# Wifi.net
KiCad netlist of a schematic drawn in Altium Designer
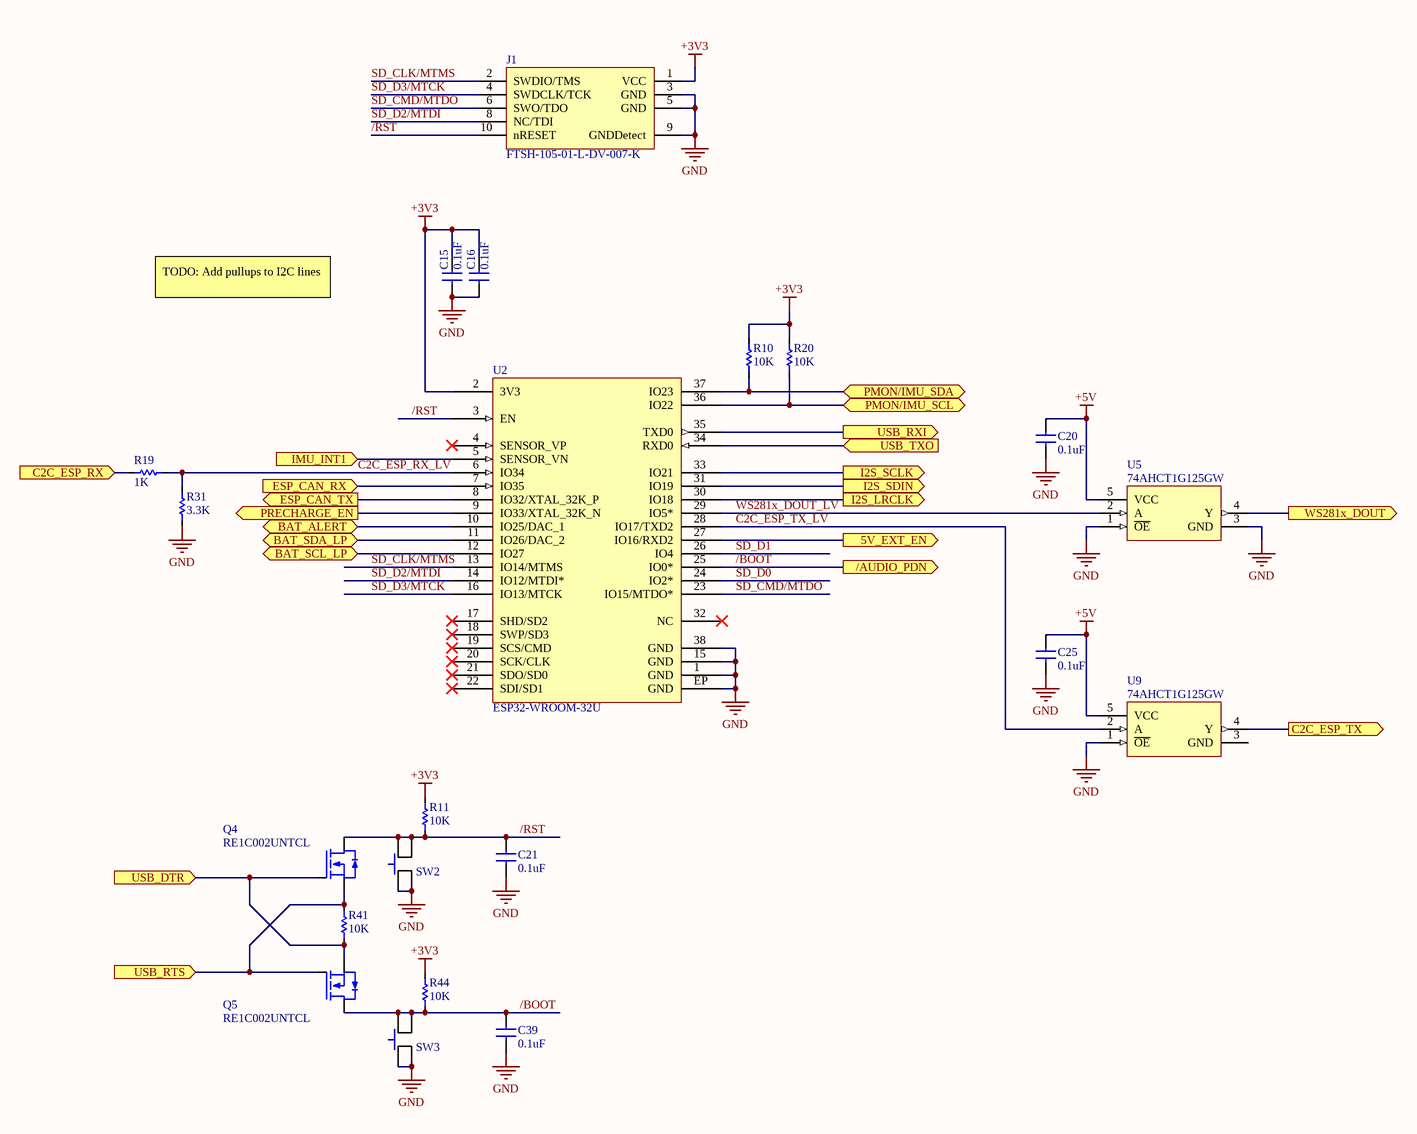
[diagram p0: Wifi.SchDoc]

(export (version "E")
  (design (tool "Eeschema 10.0.6"))
  (components
    (comp (ref "C15")
      (value "0.1uF")
      (footprint "0402_CAPACITOR")
      (description "CAP CERM 0.1uF 10% 16V 0402")
      (fields (field (name "VOLTAGE") "16V") (field (name "Comment") "CAP 0.1uF 16V X7R"))
      (libsource (lib "capacitor") (part "C_0402_0.1uF_16V_10%"))
    )
    (comp (ref "C16")
      (value "0.1uF")
      (footprint "0402_CAPACITOR")
      (description "CAP CERM 0.1uF 10% 16V 0402")
      (fields (field (name "VOLTAGE") "16V") (field (name "Comment") "CAP 0.1uF 16V X7R"))
      (libsource (lib "capacitor") (part "C_0402_0.1uF_16V_10%"))
    )
    (comp (ref "C20")
      (value "0.1uF")
      (footprint "0402_CAPACITOR")
      (description "CAP CERM 0.1uF 10% 16V 0402")
      (fields (field (name "VOLTAGE") "16V") (field (name "Comment") "CAP 0.1uF 16V X7R"))
      (libsource (lib "capacitor") (part "C_0402_0.1uF_16V_10%"))
    )
    (comp (ref "C21")
      (value "0.1uF")
      (footprint "0402_CAPACITOR")
      (description "CAP CERM 0.1uF 10% 16V 0402")
      (fields (field (name "VOLTAGE") "16V") (field (name "Comment") "CAP 0.1uF 16V X7R"))
      (libsource (lib "capacitor") (part "C_0402_0.1uF_16V_10%"))
    )
    (comp (ref "C25")
      (value "0.1uF")
      (footprint "0402_CAPACITOR")
      (description "CAP CERM 0.1uF 10% 16V 0402")
      (fields (field (name "VOLTAGE") "16V") (field (name "Comment") "CAP 0.1uF 16V X7R"))
      (libsource (lib "capacitor") (part "C_0402_0.1uF_16V_10%"))
    )
    (comp (ref "C39")
      (value "0.1uF")
      (footprint "0402_CAPACITOR")
      (description "CAP CERM 0.1uF 10% 16V 0402")
      (fields (field (name "VOLTAGE") "16V") (field (name "Comment") "CAP 0.1uF 16V X7R"))
      (libsource (lib "capacitor") (part "C_0402_0.1uF_16V_10%"))
    )
    (comp (ref "J1")
      (value "FTSH-105-01-L-DV-007-K")
      (footprint "J_Cortex_JTAG_SMD")
      (description "CORTEX JTAG DEBUG CONNECTOR")
      (fields (field (name "MANUFACTURER") "Samtec Inc"))
      (libsource (lib "connector") (part "J_Cortex_JTAG_SMD"))
    )
    (comp (ref "Q4")
      (value "RE1C002UNTCL")
      (footprint "EMT3F")
      (description "N-Channel 20V 200mA (Ta) 150mW (Ta) Surface Mount EMT3F (SOT-416FL)")
      (fields (field (name "MANUFACTURER") "Rohm"))
      (libsource (lib "transistor") (part "Q_RE1C002UNTCL"))
    )
    (comp (ref "Q5")
      (value "RE1C002UNTCL")
      (footprint "EMT3F")
      (description "N-Channel 20V 200mA (Ta) 150mW (Ta) Surface Mount EMT3F (SOT-416FL)")
      (fields (field (name "MANUFACTURER") "Rohm"))
      (libsource (lib "transistor") (part "Q_RE1C002UNTCL"))
    )
    (comp (ref "R10")
      (value "10K")
      (footprint "0402_Resistor")
      (description "Generic 0402 Resistor (10.2R to 10M)")
      (fields (field (name "TOLERANCE") "±1%") (field (name "MANUFACTURER") "Yageo"))
      (libsource (lib "resistor") (part "R_0402_generic_1%"))
    )
    (comp (ref "R11")
      (value "10K")
      (footprint "0402_Resistor")
      (description "Generic 0402 Resistor (10.2R to 10M)")
      (fields (field (name "TOLERANCE") "±1%") (field (name "MANUFACTURER") "Yageo"))
      (libsource (lib "resistor") (part "R_0402_generic_1%"))
    )
    (comp (ref "R19")
      (value "1K")
      (footprint "0402_Resistor")
      (description "Generic 0402 Resistor (10.2R to 10M)")
      (fields (field (name "TOLERANCE") "±1%") (field (name "MANUFACTURER") "Yageo"))
      (libsource (lib "resistor") (part "R_0402_generic_1%"))
    )
    (comp (ref "R20")
      (value "10K")
      (footprint "0402_Resistor")
      (description "Generic 0402 Resistor (10.2R to 10M)")
      (fields (field (name "TOLERANCE") "±1%") (field (name "MANUFACTURER") "Yageo"))
      (libsource (lib "resistor") (part "R_0402_generic_1%"))
    )
    (comp (ref "R31")
      (value "3.3K")
      (footprint "0402_Resistor")
      (description "Generic 0402 Resistor (10.2R to 10M)")
      (fields (field (name "TOLERANCE") "±1%") (field (name "MANUFACTURER") "Yageo"))
      (libsource (lib "resistor") (part "R_0402_generic_1%"))
    )
    (comp (ref "R41")
      (value "10K")
      (footprint "0402_Resistor")
      (description "Generic 0402 Resistor (10.2R to 10M)")
      (fields (field (name "TOLERANCE") "±1%") (field (name "MANUFACTURER") "Yageo"))
      (libsource (lib "resistor") (part "R_0402_generic_1%"))
    )
    (comp (ref "R44")
      (value "10K")
      (footprint "0402_Resistor")
      (description "Generic 0402 Resistor (10.2R to 10M)")
      (fields (field (name "TOLERANCE") "±1%") (field (name "MANUFACTURER") "Yageo"))
      (libsource (lib "resistor") (part "R_0402_generic_1%"))
    )
    (comp (ref "SW2")
      (value "KSEM31J_LFS")
      (footprint "SW_6x6mm_SMD")
      (description "Tactile Switch SPST-NO Top Actuated Surface Mount")
      (libsource (lib "misc") (part "SW_KSEM31J_LFS"))
    )
    (comp (ref "SW3")
      (value "KSEM31J_LFS")
      (footprint "SW_6x6mm_SMD")
      (description "Tactile Switch SPST-NO Top Actuated Surface Mount")
      (libsource (lib "misc") (part "SW_KSEM31J_LFS"))
    )
    (comp (ref "U2")
      (value "ESP32-WROOM-32U")
      (footprint "U_ESP32-WROOM-32U")
      (libsource (lib "ic") (part "U_ESP32-WROOM-32U"))
    )
    (comp (ref "U5")
      (value "74AHCT1G125GW")
      (footprint "SC70-5")
      (description "Buffer, Non-Inverting 1 Element 1 Bit per Element 3-State Output 5-TSSOP")
      (fields (field (name "MANUFACTURER") "NXP Semiconductors"))
      (libsource (lib "ic") (part "U_74AHCT1G125GW"))
    )
    (comp (ref "U9")
      (value "74AHCT1G125GW")
      (footprint "SC70-5")
      (description "Buffer, Non-Inverting 1 Element 1 Bit per Element 3-State Output 5-TSSOP")
      (fields (field (name "MANUFACTURER") "NXP Semiconductors"))
      (libsource (lib "ic") (part "U_74AHCT1G125GW"))
    )
  )
  (nets
    (net (code "1") (name "+3V3") (class "Default")
      (node (ref "C15") (pin "1") (pinfunction "1_1") (pintype "passive"))
      (node (ref "C16") (pin "1") (pinfunction "1_1") (pintype "passive"))
      (node (ref "J1") (pin "1") (pinfunction "VCC_1") (pintype "passive"))
      (node (ref "R10") (pin "1") (pinfunction "1_1") (pintype "passive"))
      (node (ref "R11") (pin "1") (pinfunction "1_1") (pintype "passive"))
      (node (ref "R20") (pin "1") (pinfunction "1_1") (pintype "passive"))
      (node (ref "R44") (pin "1") (pinfunction "1_1") (pintype "passive"))
      (node (ref "U2") (pin "2") (pinfunction "3V3_2") (pintype "power_in"))
    )
    (net (code "2") (name "+5V") (class "Default")
      (node (ref "C20") (pin "2") (pinfunction "2_2") (pintype "passive"))
      (node (ref "C25") (pin "2") (pinfunction "2_2") (pintype "passive"))
      (node (ref "U5") (pin "5") (pinfunction "VCC_5") (pintype "power_in"))
      (node (ref "U9") (pin "5") (pinfunction "VCC_5") (pintype "power_in"))
    )
    (net (code "3") (name "/5V_EXT_EN") (class "Default")
      (node (ref "U2") (pin "27") (pinfunction "IO16/RXD2_27") (pintype "passive"))
    )
    (net (code "4") (name "/BAT_ALERT") (class "Default")
      (node (ref "U2") (pin "10") (pinfunction "IO25/DAC_1_10") (pintype "passive"))
    )
    (net (code "5") (name "/BAT_SCL_LP") (class "Default")
      (node (ref "U2") (pin "12") (pinfunction "IO27_12") (pintype "passive"))
    )
    (net (code "6") (name "/BAT_SDA_LP") (class "Default")
      (node (ref "U2") (pin "11") (pinfunction "IO26/DAC_2_11") (pintype "passive"))
    )
    (net (code "7") (name "/C2C_ESP_RX") (class "Default")
      (node (ref "R19") (pin "1") (pinfunction "1_1") (pintype "passive"))
    )
    (net (code "8") (name "/C2C_ESP_RX_LV") (class "Default")
      (node (ref "R19") (pin "2") (pinfunction "2_2") (pintype "passive"))
      (node (ref "R31") (pin "2") (pinfunction "2_2") (pintype "passive"))
      (node (ref "U2") (pin "6") (pinfunction "IO34_6") (pintype "input"))
    )
    (net (code "9") (name "/C2C_ESP_TX") (class "Default")
      (node (ref "U9") (pin "4") (pinfunction "Y_4") (pintype "output"))
    )
    (net (code "10") (name "/C2C_ESP_TX_LV") (class "Default")
      (node (ref "U2") (pin "28") (pinfunction "IO17/TXD2_28") (pintype "passive"))
      (node (ref "U9") (pin "2") (pinfunction "A_2") (pintype "input"))
    )
    (net (code "11") (name "/ESP_CAN_RX") (class "Default")
      (node (ref "U2") (pin "7") (pinfunction "IO35_7") (pintype "input"))
    )
    (net (code "12") (name "/ESP_CAN_TX") (class "Default")
      (node (ref "U2") (pin "8") (pinfunction "IO32/XTAL_32K_P_8") (pintype "passive"))
    )
    (net (code "13") (name "/I2S_LRCLK") (class "Default")
      (node (ref "U2") (pin "30") (pinfunction "IO18_30") (pintype "passive"))
    )
    (net (code "14") (name "/I2S_SCLK") (class "Default")
      (node (ref "U2") (pin "33") (pinfunction "IO21_33") (pintype "passive"))
    )
    (net (code "15") (name "/I2S_SDIN") (class "Default")
      (node (ref "U2") (pin "31") (pinfunction "IO19_31") (pintype "passive"))
    )
    (net (code "16") (name "/IMU_INT1") (class "Default")
      (node (ref "U2") (pin "5") (pinfunction "SENSOR_VN_5") (pintype "input"))
    )
    (net (code "17") (name "/PMON{slash}IMU_SCL") (class "Default")
      (node (ref "R20") (pin "2") (pinfunction "2_2") (pintype "passive"))
      (node (ref "U2") (pin "36") (pinfunction "IO22_36") (pintype "passive"))
    )
    (net (code "18") (name "/PMON{slash}IMU_SDA") (class "Default")
      (node (ref "R10") (pin "2") (pinfunction "2_2") (pintype "passive"))
      (node (ref "U2") (pin "37") (pinfunction "IO23_37") (pintype "passive"))
    )
    (net (code "19") (name "/PRECHARGE_EN") (class "Default")
      (node (ref "U2") (pin "9") (pinfunction "IO33/XTAL_32K_N_9") (pintype "passive"))
    )
    (net (code "20") (name "/SD_CLK{slash}MTMS") (class "Default")
      (node (ref "J1") (pin "2") (pinfunction "SWDIO/TMS_2") (pintype "passive"))
      (node (ref "U2") (pin "13") (pinfunction "IO14/MTMS_13") (pintype "passive"))
    )
    (net (code "21") (name "/SD_CMD{slash}MTDO") (class "Default")
      (node (ref "J1") (pin "6") (pinfunction "SWO/TDO_6") (pintype "passive"))
      (node (ref "U2") (pin "23") (pinfunction "IO15/MTDO*_23") (pintype "passive"))
    )
    (net (code "22") (name "/SD_D0") (class "Default")
      (node (ref "U2") (pin "24") (pinfunction "IO2*_24") (pintype "passive"))
    )
    (net (code "23") (name "/SD_D1") (class "Default")
      (node (ref "U2") (pin "26") (pinfunction "IO4_26") (pintype "passive"))
    )
    (net (code "24") (name "/SD_D2{slash}MTDI") (class "Default")
      (node (ref "J1") (pin "8") (pinfunction "NC/TDI_8") (pintype "passive"))
      (node (ref "U2") (pin "14") (pinfunction "IO12/MTDI*_14") (pintype "passive"))
    )
    (net (code "25") (name "/SD_D3{slash}MTCK") (class "Default")
      (node (ref "J1") (pin "4") (pinfunction "SWDCLK/TCK_4") (pintype "passive"))
      (node (ref "U2") (pin "16") (pinfunction "IO13/MTCK_16") (pintype "passive"))
    )
    (net (code "26") (name "/USB_DTR") (class "Default")
      (node (ref "Q4") (pin "1") (pinfunction "GATE_1") (pintype "passive"))
      (node (ref "Q5") (pin "2") (pinfunction "SOURCE_2") (pintype "passive"))
      (node (ref "R41") (pin "2") (pinfunction "2_2") (pintype "passive"))
    )
    (net (code "27") (name "/USB_RTS") (class "Default")
      (node (ref "Q4") (pin "2") (pinfunction "SOURCE_2") (pintype "passive"))
      (node (ref "Q5") (pin "1") (pinfunction "GATE_1") (pintype "passive"))
      (node (ref "R41") (pin "1") (pinfunction "1_1") (pintype "passive"))
    )
    (net (code "28") (name "/USB_RXI") (class "Default")
      (node (ref "U2") (pin "35") (pinfunction "TXD0_35") (pintype "output"))
    )
    (net (code "29") (name "/USB_TXO") (class "Default")
      (node (ref "U2") (pin "34") (pinfunction "RXD0_34") (pintype "input"))
    )
    (net (code "30") (name "/WS281x_DOUT") (class "Default")
      (node (ref "U5") (pin "4") (pinfunction "Y_4") (pintype "output"))
    )
    (net (code "31") (name "/WS281x_DOUT_LV") (class "Default")
      (node (ref "U2") (pin "29") (pinfunction "IO5*_29") (pintype "passive"))
      (node (ref "U5") (pin "2") (pinfunction "A_2") (pintype "input"))
    )
    (net (code "32") (name "/{slash}BOOT") (class "Default")
      (node (ref "C39") (pin "2") (pinfunction "2_2") (pintype "passive"))
      (node (ref "Q5") (pin "3") (pinfunction "DRAIN_3") (pintype "passive"))
      (node (ref "R44") (pin "2") (pinfunction "2_2") (pintype "passive"))
      (node (ref "SW3") (pin "2") (pinfunction "2_2") (pintype "passive"))
      (node (ref "SW3") (pin "3") (pinfunction "3_3") (pintype "passive"))
      (node (ref "U2") (pin "25") (pinfunction "IO0*_25") (pintype "passive"))
    )
    (net (code "33") (name "/{slash}RST") (class "Default")
      (node (ref "C21") (pin "2") (pinfunction "2_2") (pintype "passive"))
      (node (ref "J1") (pin "10") (pinfunction "nRESET_10") (pintype "passive"))
      (node (ref "Q4") (pin "3") (pinfunction "DRAIN_3") (pintype "passive"))
      (node (ref "R11") (pin "2") (pinfunction "2_2") (pintype "passive"))
      (node (ref "SW2") (pin "2") (pinfunction "2_2") (pintype "passive"))
      (node (ref "SW2") (pin "3") (pinfunction "3_3") (pintype "passive"))
      (node (ref "U2") (pin "3") (pinfunction "EN_3") (pintype "input"))
    )
    (net (code "34") (name "GND") (class "Default")
      (node (ref "C15") (pin "2") (pinfunction "2_2") (pintype "passive"))
      (node (ref "C16") (pin "2") (pinfunction "2_2") (pintype "passive"))
      (node (ref "C20") (pin "1") (pinfunction "1_1") (pintype "passive"))
      (node (ref "C21") (pin "1") (pinfunction "1_1") (pintype "passive"))
      (node (ref "C25") (pin "1") (pinfunction "1_1") (pintype "passive"))
      (node (ref "C39") (pin "1") (pinfunction "1_1") (pintype "passive"))
      (node (ref "J1") (pin "3") (pinfunction "GND_3") (pintype "passive"))
      (node (ref "J1") (pin "5") (pinfunction "GND_5") (pintype "passive"))
      (node (ref "J1") (pin "9") (pinfunction "GNDDetect_9") (pintype "passive"))
      (node (ref "R31") (pin "1") (pinfunction "1_1") (pintype "passive"))
      (node (ref "SW2") (pin "1") (pinfunction "1_1") (pintype "passive"))
      (node (ref "SW2") (pin "4") (pinfunction "4_4") (pintype "passive"))
      (node (ref "SW3") (pin "1") (pinfunction "1_1") (pintype "passive"))
      (node (ref "SW3") (pin "4") (pinfunction "4_4") (pintype "passive"))
      (node (ref "U2") (pin "1") (pinfunction "GND_1") (pintype "power_in"))
      (node (ref "U2") (pin "15") (pinfunction "GND_15") (pintype "power_in"))
      (node (ref "U2") (pin "38") (pinfunction "GND_38") (pintype "power_in"))
      (node (ref "U2") (pin "EP") (pinfunction "GND_EP") (pintype "power_in"))
      (node (ref "U5") (pin "1") (pinfunction "~{OE}_1") (pintype "input"))
      (node (ref "U5") (pin "3") (pinfunction "GND_3") (pintype "power_in"))
      (node (ref "U9") (pin "1") (pinfunction "~{OE}_1") (pintype "input"))
    )
    (net (code "35") (name "unconnected-(U2-NC-Pad32)") (class "Default")
      (node (ref "U2") (pin "32") (pinfunction "NC_32") (pintype "tri_state+no_connect"))
    )
    (net (code "36") (name "unconnected-(U2-SCK{slash}CLK-Pad20)") (class "Default")
      (node (ref "U2") (pin "20") (pinfunction "SCK/CLK_20") (pintype "passive+no_connect"))
    )
    (net (code "37") (name "unconnected-(U2-SCS{slash}CMD-Pad19)") (class "Default")
      (node (ref "U2") (pin "19") (pinfunction "SCS/CMD_19") (pintype "passive+no_connect"))
    )
    (net (code "38") (name "unconnected-(U2-SDI{slash}SD1-Pad22)") (class "Default")
      (node (ref "U2") (pin "22") (pinfunction "SDI/SD1_22") (pintype "passive+no_connect"))
    )
    (net (code "39") (name "unconnected-(U2-SDO{slash}SD0-Pad21)") (class "Default")
      (node (ref "U2") (pin "21") (pinfunction "SDO/SD0_21") (pintype "passive+no_connect"))
    )
    (net (code "40") (name "unconnected-(U2-SENSOR_VP-Pad4)") (class "Default")
      (node (ref "U2") (pin "4") (pinfunction "SENSOR_VP_4") (pintype "input+no_connect"))
    )
    (net (code "41") (name "unconnected-(U2-SHD{slash}SD2-Pad17)") (class "Default")
      (node (ref "U2") (pin "17") (pinfunction "SHD/SD2_17") (pintype "passive+no_connect"))
    )
    (net (code "42") (name "unconnected-(U2-SWP{slash}SD3-Pad18)") (class "Default")
      (node (ref "U2") (pin "18") (pinfunction "SWP/SD3_18") (pintype "passive+no_connect"))
    )
    (net (code "43") (name "unconnected-(U9-GND-Pad3)") (class "Default")
      (node (ref "U9") (pin "3") (pinfunction "GND_3") (pintype "power_in"))
    )
  )
)
